# RC_RX_CABELL_V3_FHSS_With_Diversity.net
KiCad netlist of a schematic drawn in EAGLE
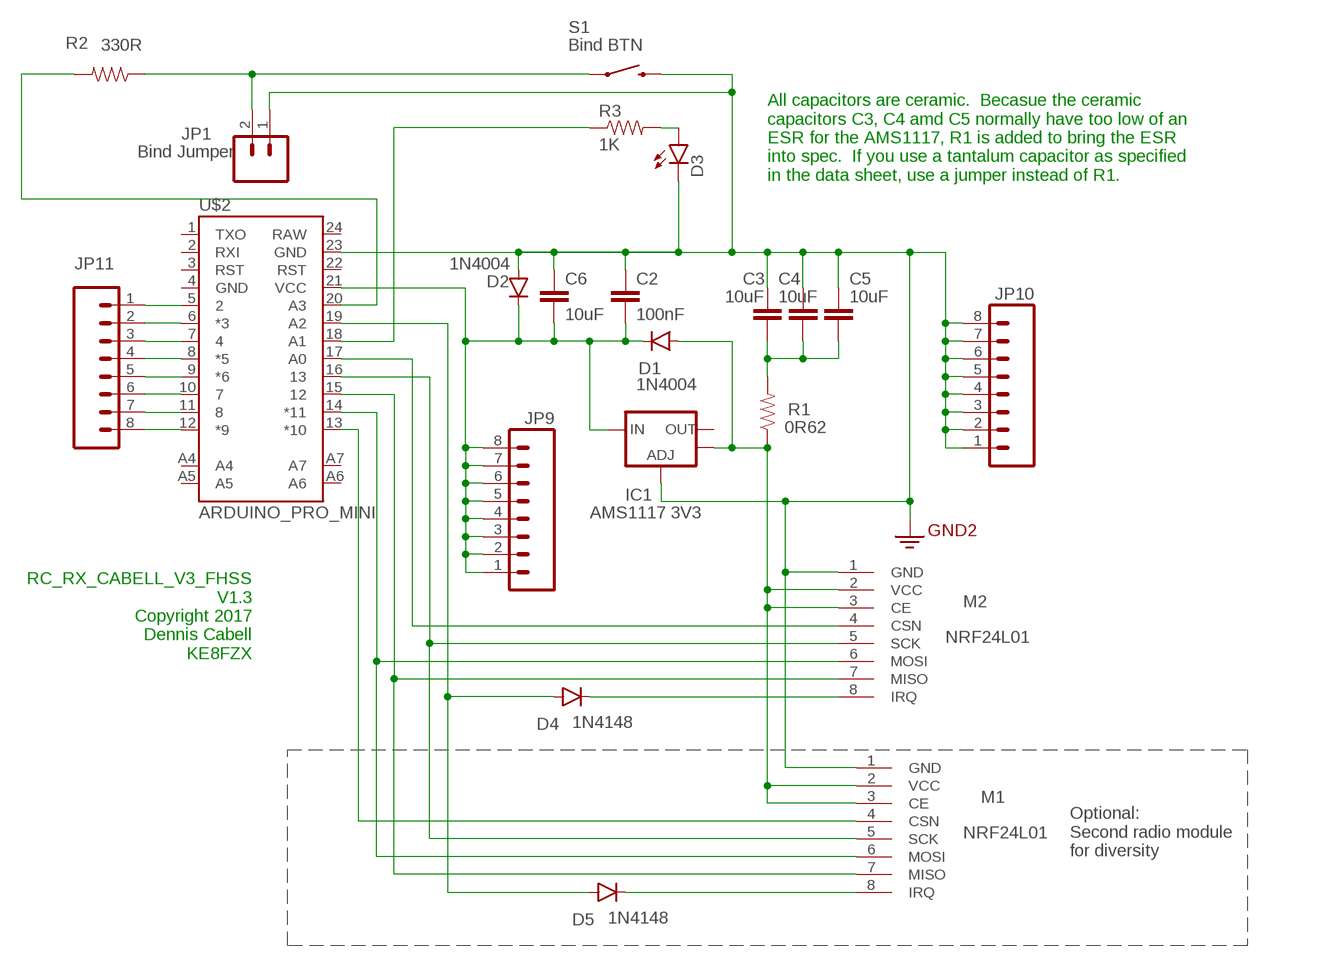
[diagram p0: schematic, sheet 1]

(export (version "E")
  (design (tool "Eeschema 10.0.6"))
  (components
    (comp (ref "C2")
      (value "100nF")
      (footprint "eagle-import:CAP-PTH-5MM")
      (libsource (lib "eagle-import") (part "CAPPTH1"))
    )
    (comp (ref "C3")
      (value "10uF")
      (footprint "eagle-import:CAP-PTH-5MM")
      (libsource (lib "eagle-import") (part "CAPPTH1"))
    )
    (comp (ref "C4")
      (value "10uF")
      (footprint "eagle-import:CAP-PTH-5MM")
      (libsource (lib "eagle-import") (part "CAPPTH1"))
    )
    (comp (ref "C5")
      (value "10uF")
      (footprint "eagle-import:CAP-PTH-5MM")
      (libsource (lib "eagle-import") (part "CAPPTH1"))
    )
    (comp (ref "C6")
      (value "10uF")
      (footprint "eagle-import:CAP-PTH-5MM")
      (libsource (lib "eagle-import") (part "CAPPTH1"))
    )
    (comp (ref "D1")
      (value "1N4004")
      (footprint "eagle-import:DIODE-1N4001")
      (libsource (lib "eagle-import") (part "DIODEPTH"))
    )
    (comp (ref "D2")
      (value "1N4004")
      (footprint "eagle-import:DIODE-1N4001")
      (libsource (lib "eagle-import") (part "DIODEPTH"))
    )
    (comp (ref "D3")
      (value "LED3MM")
      (footprint "eagle-import:LED3MM")
      (libsource (lib "eagle-import") (part "LED3MM"))
    )
    (comp (ref "D4")
      (value "1N4148")
      (footprint "eagle-import:DIODE-1N4148")
      (libsource (lib "eagle-import") (part "DIODE1N4148"))
    )
    (comp (ref "D5")
      (value "1N4148")
      (footprint "eagle-import:DIODE-1N4001")
      (libsource (lib "eagle-import") (part "DIODEPTH"))
    )
    (comp (ref "IC1")
      (value "AMS1117 3V3")
      (footprint "eagle-import:SOT223")
      (libsource (lib "eagle-import") (part "V_REG_LM1117SOT223"))
    )
    (comp (ref "JP1")
      (value "Bind Jumper")
      (footprint "eagle-import:1X02")
      (libsource (lib "eagle-import") (part "M02PTH"))
    )
    (comp (ref "JP9")
      (value "M08")
      (footprint "eagle-import:1X08_ROUND")
      (libsource (lib "eagle-import") (part "M08"))
    )
    (comp (ref "JP10")
      (value "M08")
      (footprint "eagle-import:1X08_ROUND")
      (libsource (lib "eagle-import") (part "M08"))
    )
    (comp (ref "JP11")
      (value "M08")
      (footprint "eagle-import:1X08_ROUND")
      (libsource (lib "eagle-import") (part "M08"))
    )
    (comp (ref "M1")
      (value "NRF24L01")
      (footprint "eagle-import:WIRELESS-NRF24L01")
      (libsource (lib "eagle-import") (part "WIRELESS-NRF24L01"))
    )
    (comp (ref "M2")
      (value "NRF24L01")
      (footprint "eagle-import:WIRELESS-NRF24L01")
      (libsource (lib "eagle-import") (part "WIRELESS-NRF24L01"))
    )
    (comp (ref "R1")
      (value "0R62")
      (footprint "eagle-import:AXIAL-0.5")
      (libsource (lib "eagle-import") (part "RESISTORPTH-1/2W"))
    )
    (comp (ref "R2")
      (value "330R")
      (footprint "eagle-import:AXIAL-0.3")
      (libsource (lib "eagle-import") (part "RESISTORAXIAL-0.3"))
    )
    (comp (ref "R3")
      (value "1K")
      (footprint "eagle-import:AXIAL-0.3")
      (libsource (lib "eagle-import") (part "RESISTORAXIAL-0.3"))
    )
    (comp (ref "S1")
      (value "Bind BTN")
      (footprint "eagle-import:TACTILE-SWITCH-1101NE")
      (libsource (lib "eagle-import") (part "SWITCH-MOMENTARY-2SMD-1101NE"))
    )
    (comp (ref "U$2")
      (value "ARDUINO_PRO_MINI")
      (footprint "eagle-import:ARDUINO_PRO_MINI")
      (libsource (lib "eagle-import") (part "ARDUINO_PRO_MINI"))
    )
  )
  (nets
    (net (code "1") (name "GND2") (class "Default")
      (node (ref "C2") (pin "1") (pinfunction "1_1") (pintype "passive"))
      (node (ref "C3") (pin "1") (pinfunction "1_1") (pintype "passive"))
      (node (ref "C4") (pin "1") (pinfunction "1_1") (pintype "passive"))
      (node (ref "C5") (pin "1") (pinfunction "1_1") (pintype "passive"))
      (node (ref "C6") (pin "1") (pinfunction "1_1") (pintype "passive"))
      (node (ref "D2") (pin "A") (pinfunction "A_A") (pintype "passive"))
      (node (ref "D3") (pin "K") (pinfunction "C_K") (pintype "passive"))
      (node (ref "IC1") (pin "1") (pinfunction "ADJ_1") (pintype "input"))
      (node (ref "JP1") (pin "1") (pinfunction "1_1") (pintype "passive"))
      (node (ref "JP10") (pin "1") (pinfunction "1_1") (pintype "passive"))
      (node (ref "JP10") (pin "2") (pinfunction "2_2") (pintype "passive"))
      (node (ref "JP10") (pin "3") (pinfunction "3_3") (pintype "passive"))
      (node (ref "JP10") (pin "4") (pinfunction "4_4") (pintype "passive"))
      (node (ref "JP10") (pin "5") (pinfunction "5_5") (pintype "passive"))
      (node (ref "JP10") (pin "6") (pinfunction "6_6") (pintype "passive"))
      (node (ref "JP10") (pin "7") (pinfunction "7_7") (pintype "passive"))
      (node (ref "JP10") (pin "8") (pinfunction "8_8") (pintype "passive"))
      (node (ref "M1") (pin "1") (pinfunction "GND_1") (pintype "power_in"))
      (node (ref "M2") (pin "1") (pinfunction "GND_1") (pintype "power_in"))
      (node (ref "S1") (pin "2") (pinfunction "2_2") (pintype "passive"))
      (node (ref "U$2") (pin "23") (pinfunction "GND_23") (pintype "bidirectional"))
    )
    (net (code "2") (name "Net-(IC1-IN)") (class "Default")
      (node (ref "C2") (pin "2") (pinfunction "2_2") (pintype "passive"))
      (node (ref "C6") (pin "2") (pinfunction "2_2") (pintype "passive"))
      (node (ref "D1") (pin "C") (pinfunction "C_C") (pintype "passive"))
      (node (ref "D2") (pin "C") (pinfunction "C_C") (pintype "passive"))
      (node (ref "IC1") (pin "3") (pinfunction "IN_3") (pintype "input"))
      (node (ref "JP9") (pin "1") (pinfunction "1_1") (pintype "passive"))
      (node (ref "JP9") (pin "2") (pinfunction "2_2") (pintype "passive"))
      (node (ref "JP9") (pin "3") (pinfunction "3_3") (pintype "passive"))
      (node (ref "JP9") (pin "4") (pinfunction "4_4") (pintype "passive"))
      (node (ref "JP9") (pin "5") (pinfunction "5_5") (pintype "passive"))
      (node (ref "JP9") (pin "6") (pinfunction "6_6") (pintype "passive"))
      (node (ref "JP9") (pin "7") (pinfunction "7_7") (pintype "passive"))
      (node (ref "JP9") (pin "8") (pinfunction "8_8") (pintype "passive"))
      (node (ref "U$2") (pin "21") (pinfunction "VCC_21") (pintype "bidirectional"))
    )
    (net (code "3") (name "Net-(M1-CE)") (class "Default")
      (node (ref "D1") (pin "A") (pinfunction "A_A") (pintype "passive"))
      (node (ref "IC1") (pin "4") (pinfunction "OUT_4") (pintype "output"))
      (node (ref "M1") (pin "2") (pinfunction "VCC_2") (pintype "power_in"))
      (node (ref "M1") (pin "3") (pinfunction "CE_3") (pintype "bidirectional"))
      (node (ref "M2") (pin "2") (pinfunction "VCC_2") (pintype "power_in"))
      (node (ref "M2") (pin "3") (pinfunction "CE_3") (pintype "bidirectional"))
      (node (ref "R1") (pin "P$1") (pinfunction "1_P$1") (pintype "passive"))
    )
    (net (code "4") (name "Net-(M1-CSN)") (class "Default")
      (node (ref "M1") (pin "4") (pinfunction "CSN_4") (pintype "bidirectional"))
      (node (ref "U$2") (pin "13") (pinfunction "*10_13") (pintype "bidirectional"))
    )
    (net (code "5") (name "Net-(M1-IRQ)") (class "Default")
      (node (ref "D5") (pin "C") (pinfunction "C_C") (pintype "passive"))
      (node (ref "M1") (pin "8") (pinfunction "IRQ_8") (pintype "bidirectional"))
    )
    (net (code "6") (name "Net-(M1-MISO)") (class "Default")
      (node (ref "M1") (pin "7") (pinfunction "MISO_7") (pintype "bidirectional"))
      (node (ref "M2") (pin "7") (pinfunction "MISO_7") (pintype "bidirectional"))
      (node (ref "U$2") (pin "15") (pinfunction "12_15") (pintype "bidirectional"))
    )
    (net (code "7") (name "Net-(M1-MOSI)") (class "Default")
      (node (ref "M1") (pin "6") (pinfunction "MOSI_6") (pintype "bidirectional"))
      (node (ref "M2") (pin "6") (pinfunction "MOSI_6") (pintype "bidirectional"))
      (node (ref "U$2") (pin "14") (pinfunction "*11_14") (pintype "bidirectional"))
    )
    (net (code "8") (name "Net-(M1-SCK)") (class "Default")
      (node (ref "M1") (pin "5") (pinfunction "SCK_5") (pintype "bidirectional"))
      (node (ref "M2") (pin "5") (pinfunction "SCK_5") (pintype "bidirectional"))
      (node (ref "U$2") (pin "16") (pinfunction "13_16") (pintype "bidirectional"))
    )
    (net (code "9") (name "Net-(M2-CSN)") (class "Default")
      (node (ref "M2") (pin "4") (pinfunction "CSN_4") (pintype "bidirectional"))
      (node (ref "U$2") (pin "17") (pinfunction "A0_17") (pintype "bidirectional"))
    )
    (net (code "10") (name "Net-(M2-IRQ)") (class "Default")
      (node (ref "D4") (pin "C") (pinfunction "C_C") (pintype "passive"))
      (node (ref "M2") (pin "8") (pinfunction "IRQ_8") (pintype "bidirectional"))
    )
    (net (code "11") (name "Net-(R1-2)") (class "Default")
      (node (ref "C3") (pin "2") (pinfunction "2_2") (pintype "passive"))
      (node (ref "C4") (pin "2") (pinfunction "2_2") (pintype "passive"))
      (node (ref "C5") (pin "2") (pinfunction "2_2") (pintype "passive"))
      (node (ref "R1") (pin "P$2") (pinfunction "2_P$2") (pintype "passive"))
    )
    (net (code "12") (name "Net-(R2-1)") (class "Default")
      (node (ref "JP1") (pin "2") (pinfunction "2_2") (pintype "passive"))
      (node (ref "R2") (pin "P$1") (pinfunction "1_P$1") (pintype "passive"))
      (node (ref "S1") (pin "1") (pinfunction "1_1") (pintype "passive"))
    )
    (net (code "13") (name "Net-(R2-2)") (class "Default")
      (node (ref "R2") (pin "P$2") (pinfunction "2_P$2") (pintype "passive"))
      (node (ref "U$2") (pin "20") (pinfunction "A3_20") (pintype "bidirectional"))
    )
    (net (code "14") (name "Net-(R3-1)") (class "Default")
      (node (ref "R3") (pin "P$1") (pinfunction "1_P$1") (pintype "passive"))
      (node (ref "U$2") (pin "18") (pinfunction "A1_18") (pintype "bidirectional"))
    )
    (net (code "15") (name "Net-(R3-2)") (class "Default")
      (node (ref "D3") (pin "A") (pinfunction "A_A") (pintype "passive"))
      (node (ref "R3") (pin "P$2") (pinfunction "2_P$2") (pintype "passive"))
    )
    (net (code "16") (name "Net-(U$2-*3)") (class "Default")
      (node (ref "JP11") (pin "2") (pinfunction "2_2") (pintype "passive"))
      (node (ref "U$2") (pin "6") (pinfunction "*3_6") (pintype "bidirectional"))
    )
    (net (code "17") (name "Net-(U$2-*5)") (class "Default")
      (node (ref "JP11") (pin "4") (pinfunction "4_4") (pintype "passive"))
      (node (ref "U$2") (pin "8") (pinfunction "*5_8") (pintype "bidirectional"))
    )
    (net (code "18") (name "Net-(U$2-*6)") (class "Default")
      (node (ref "JP11") (pin "5") (pinfunction "5_5") (pintype "passive"))
      (node (ref "U$2") (pin "9") (pinfunction "*6_9") (pintype "bidirectional"))
    )
    (net (code "19") (name "Net-(U$2-*9)") (class "Default")
      (node (ref "JP11") (pin "8") (pinfunction "8_8") (pintype "passive"))
      (node (ref "U$2") (pin "12") (pinfunction "*9_12") (pintype "bidirectional"))
    )
    (net (code "20") (name "Net-(U$2-2)") (class "Default")
      (node (ref "JP11") (pin "1") (pinfunction "1_1") (pintype "passive"))
      (node (ref "U$2") (pin "5") (pinfunction "2_5") (pintype "bidirectional"))
    )
    (net (code "21") (name "Net-(U$2-4)") (class "Default")
      (node (ref "JP11") (pin "3") (pinfunction "3_3") (pintype "passive"))
      (node (ref "U$2") (pin "7") (pinfunction "4_7") (pintype "bidirectional"))
    )
    (net (code "22") (name "Net-(U$2-7)") (class "Default")
      (node (ref "JP11") (pin "6") (pinfunction "6_6") (pintype "passive"))
      (node (ref "U$2") (pin "10") (pinfunction "7_10") (pintype "bidirectional"))
    )
    (net (code "23") (name "Net-(U$2-8)") (class "Default")
      (node (ref "JP11") (pin "7") (pinfunction "7_7") (pintype "passive"))
      (node (ref "U$2") (pin "11") (pinfunction "8_11") (pintype "bidirectional"))
    )
    (net (code "24") (name "Net-(U$2-A2)") (class "Default")
      (node (ref "D4") (pin "A") (pinfunction "A_A") (pintype "passive"))
      (node (ref "D5") (pin "A") (pinfunction "A_A") (pintype "passive"))
      (node (ref "U$2") (pin "19") (pinfunction "A2_19") (pintype "bidirectional"))
    )
    (net (code "25") (name "unconnected-(IC1-OUT-Pad2)") (class "Default")
      (node (ref "IC1") (pin "2") (pinfunction "OUT_2") (pintype "output"))
    )
    (net (code "26") (name "unconnected-(U$2-GND-Pad4)") (class "Default")
      (node (ref "U$2") (pin "4") (pinfunction "GND_4") (pintype "bidirectional"))
    )
    (net (code "27") (name "unconnected-(U$2-PadA4)") (class "Default")
      (node (ref "U$2") (pin "A4") (pinfunction "A4_A4") (pintype "bidirectional"))
    )
    (net (code "28") (name "unconnected-(U$2-PadA5)") (class "Default")
      (node (ref "U$2") (pin "A5") (pinfunction "A5_A5") (pintype "bidirectional"))
    )
    (net (code "29") (name "unconnected-(U$2-PadA6)") (class "Default")
      (node (ref "U$2") (pin "A6") (pinfunction "A6_A6") (pintype "bidirectional"))
    )
    (net (code "30") (name "unconnected-(U$2-PadA7)") (class "Default")
      (node (ref "U$2") (pin "A7") (pinfunction "A7_A7") (pintype "bidirectional"))
    )
    (net (code "31") (name "unconnected-(U$2-RAW-Pad24)") (class "Default")
      (node (ref "U$2") (pin "24") (pinfunction "RAW_24") (pintype "bidirectional"))
    )
    (net (code "32") (name "unconnected-(U$2-RST-Pad3)") (class "Default")
      (node (ref "U$2") (pin "3") (pinfunction "RST_3") (pintype "bidirectional"))
    )
    (net (code "33") (name "unconnected-(U$2-RST-Pad22)") (class "Default")
      (node (ref "U$2") (pin "22") (pinfunction "RST_22") (pintype "bidirectional"))
    )
    (net (code "34") (name "unconnected-(U$2-RXI-Pad2)") (class "Default")
      (node (ref "U$2") (pin "2") (pinfunction "RXI_2") (pintype "bidirectional"))
    )
    (net (code "35") (name "unconnected-(U$2-TXO-Pad1)") (class "Default")
      (node (ref "U$2") (pin "1") (pinfunction "TXO_1") (pintype "bidirectional"))
    )
  )
)
